# LightHouse.net
KiCad netlist of a schematic drawn in EAGLE
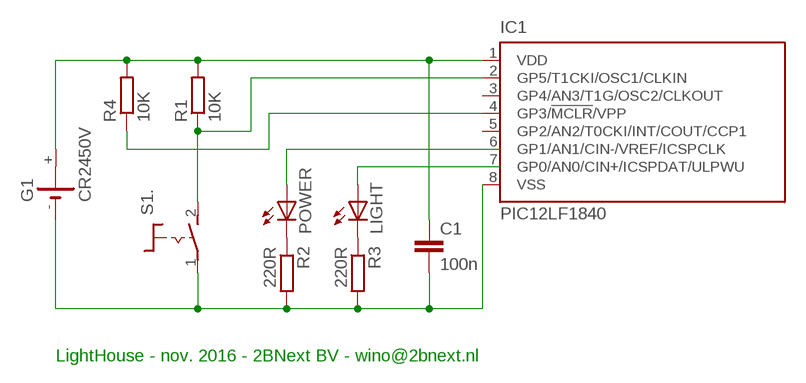
[diagram p0: schematic, sheet 1]

(export (version "E")
  (design (tool "Eeschema 10.0.6"))
  (components
    (comp (ref "C1")
      (value "100n")
      (footprint "eagle-import:C2.5-3")
      (libsource (lib "eagle-import") (part "C2,5-3"))
    )
    (comp (ref "G1")
      (value "CR2450V")
      (footprint "eagle-import:CR2450V")
      (libsource (lib "eagle-import") (part "CR2450V"))
    )
    (comp (ref "IC1")
      (value "PIC12LF1840")
      (footprint "eagle-import:DIL8")
      (fields (field (name "MF") "MICROCHIP") (field (name "MPN") "PIC12F683-I/P"))
      (libsource (lib "eagle-import") (part "PIC12F683P"))
    )
    (comp (ref "LIGHT")
      (value "LED5MM")
      (footprint "eagle-import:LED5MM")
      (libsource (lib "eagle-import") (part "LED5MM"))
    )
    (comp (ref "POWER")
      (value "LED5MM")
      (footprint "eagle-import:LED5MM")
      (libsource (lib "eagle-import") (part "LED5MM"))
    )
    (comp (ref "R1")
      (value "10K")
      (footprint "eagle-import:0204_5")
      (libsource (lib "eagle-import") (part "R-EU_0204/5"))
    )
    (comp (ref "R2")
      (value "220R")
      (footprint "eagle-import:0204_5")
      (libsource (lib "eagle-import") (part "R-EU_0204/5"))
    )
    (comp (ref "R3")
      (value "220R")
      (footprint "eagle-import:0204_5")
      (libsource (lib "eagle-import") (part "R-EU_0204/5"))
    )
    (comp (ref "R4")
      (value "10K")
      (footprint "eagle-import:0204_5")
      (libsource (lib "eagle-import") (part "R-EU_0204/5"))
    )
    (comp (ref "S1")
      (value "MARQ6425")
      (footprint "eagle-import:MARQ6425")
      (libsource (lib "eagle-import") (part "MARQ6425"))
    )
  )
  (nets
    (net (code "1") (name "Net-(IC1-GP3{slash}~{MCLR}{slash}VPP)") (class "Default")
      (node (ref "IC1") (pin "4") (pinfunction "GP3/~{MCLR}/VPP_4") (pintype "bidirectional"))
      (node (ref "R4") (pin "1") (pinfunction "1_1") (pintype "passive"))
    )
    (net (code "2") (name "Net-(IC1-GP5{slash}T1CKI{slash}OSC1{slash}CLKIN)") (class "Default")
      (node (ref "IC1") (pin "2") (pinfunction "GP5/T1CKI/OSC1/CLKIN_2") (pintype "bidirectional"))
      (node (ref "R1") (pin "1") (pinfunction "1_1") (pintype "passive"))
      (node (ref "S1") (pin "2") (pinfunction "S_2") (pintype "passive"))
    )
    (net (code "3") (name "Net-(IC1-VDD)") (class "Default")
      (node (ref "C1") (pin "1") (pinfunction "1_1") (pintype "passive"))
      (node (ref "G1") (pin "+") (pinfunction "+_+") (pintype "passive"))
      (node (ref "IC1") (pin "1") (pinfunction "VDD_1") (pintype "power_in"))
      (node (ref "R1") (pin "2") (pinfunction "2_2") (pintype "passive"))
      (node (ref "R4") (pin "2") (pinfunction "2_2") (pintype "passive"))
    )
    (net (code "4") (name "Net-(IC1-VSS)") (class "Default")
      (node (ref "C1") (pin "2") (pinfunction "2_2") (pintype "passive"))
      (node (ref "G1") (pin "-") (pinfunction "-_-") (pintype "passive"))
      (node (ref "IC1") (pin "8") (pinfunction "VSS_8") (pintype "power_in"))
      (node (ref "R2") (pin "2") (pinfunction "2_2") (pintype "passive"))
      (node (ref "R3") (pin "2") (pinfunction "2_2") (pintype "passive"))
      (node (ref "S1") (pin "1") (pinfunction "P_1") (pintype "passive"))
    )
    (net (code "5") (name "Net-(LIGHT-C)") (class "Default")
      (node (ref "LIGHT") (pin "K") (pinfunction "C_K") (pintype "passive"))
      (node (ref "R3") (pin "1") (pinfunction "1_1") (pintype "passive"))
    )
    (net (code "6") (name "Net-(POWER-C)") (class "Default")
      (node (ref "POWER") (pin "K") (pinfunction "C_K") (pintype "passive"))
      (node (ref "R2") (pin "1") (pinfunction "1_1") (pintype "passive"))
    )
    (net (code "7") (name "unconnected-(G1-+-Pad+@1)") (class "Default")
      (node (ref "G1") (pin "+@1") (pinfunction "+_+@1") (pintype "passive"))
    )
    (net (code "8") (name "unconnected-(IC1-GP0{slash}AN0{slash}CIN+{slash}ICSPDAT{slash}ULPWU-Pad7)") (class "Default")
      (node (ref "IC1") (pin "7") (pinfunction "GP0/AN0/CIN+/ICSPDAT/ULPWU_7") (pintype "bidirectional"))
    )
    (net (code "9") (name "unconnected-(IC1-GP1{slash}AN1{slash}CIN-{slash}VREF{slash}ICSPCLK-Pad6)") (class "Default")
      (node (ref "IC1") (pin "6") (pinfunction "GP1/AN1/CIN-/VREF/ICSPCLK_6") (pintype "bidirectional"))
    )
    (net (code "10") (name "unconnected-(IC1-GP2{slash}AN2{slash}T0CKI{slash}INT{slash}COUT{slash}CCP1-Pad5)") (class "Default")
      (node (ref "IC1") (pin "5") (pinfunction "GP2/AN2/T0CKI/INT/COUT/CCP1_5") (pintype "bidirectional"))
    )
    (net (code "11") (name "unconnected-(IC1-GP4{slash}AN3{slash}T1G{slash}OSC2{slash}CLKOUT-Pad3)") (class "Default")
      (node (ref "IC1") (pin "3") (pinfunction "GP4/AN3/T1G/OSC2/CLKOUT_3") (pintype "bidirectional"))
    )
    (net (code "12") (name "unconnected-(LIGHT-PadA)") (class "Default")
      (node (ref "LIGHT") (pin "A") (pinfunction "A_A") (pintype "passive"))
    )
    (net (code "13") (name "unconnected-(POWER-PadA)") (class "Default")
      (node (ref "POWER") (pin "A") (pinfunction "A_A") (pintype "passive"))
    )
  )
)
